# shield.net
KiCad netlist of a schematic drawn in EAGLE
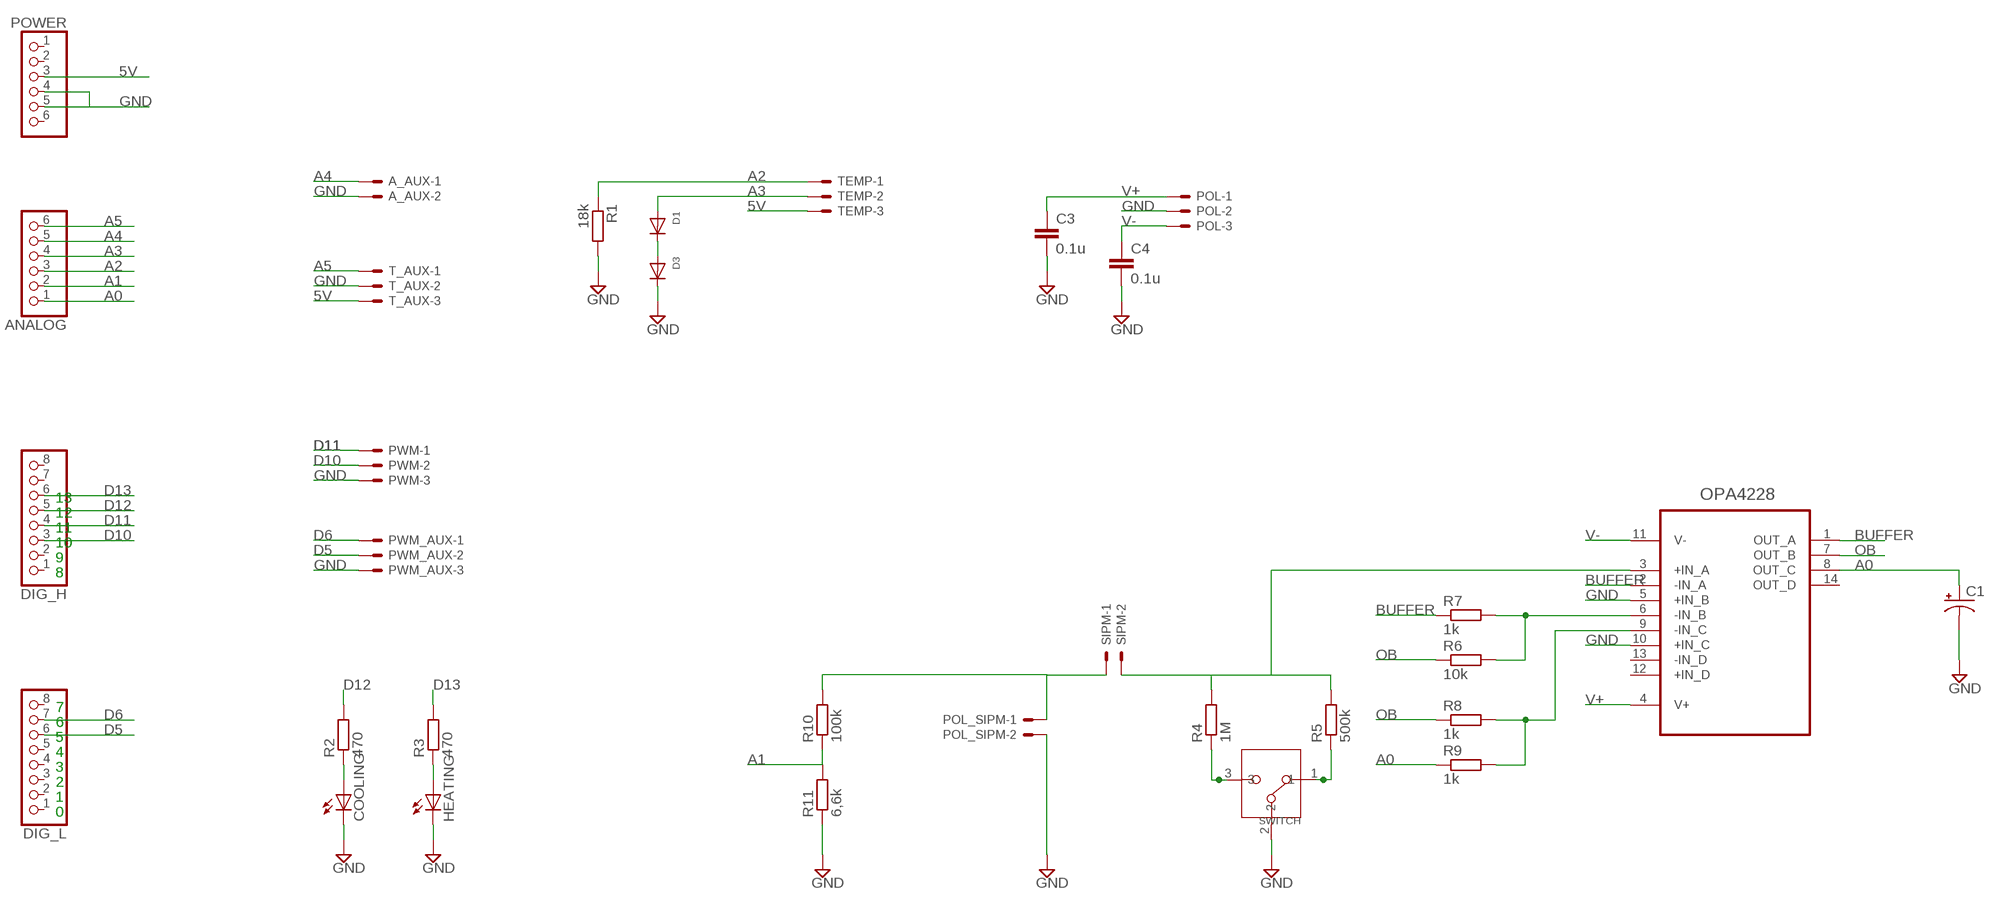
[diagram p0: schematic, sheet 1]

(export (version "E")
  (design (tool "Eeschema 10.0.6"))
  (components
    (comp (ref "ANALOG")
      (value "PINHD-1X6")
      (footprint "eagle-import:1X06")
      (libsource (lib "eagle-import") (part "PINHD-1X6"))
    )
    (comp (ref "A_AUX")
      (value "22-23-2021")
      (footprint "eagle-import:22-23-2021")
      (fields (field (name "MF") "MOLEX"))
      (libsource (lib "eagle-import") (part "22-23-2021"))
    )
    (comp (ref "C1")
      (value "CPOL-USSMCC")
      (footprint "eagle-import:SMC_C")
      (libsource (lib "eagle-import") (part "CPOL-USSMCC"))
    )
    (comp (ref "C3")
      (value "0.1u")
      (footprint "eagle-import:C0805K")
      (libsource (lib "eagle-import") (part "C-EUC0805K"))
    )
    (comp (ref "C4")
      (value "0.1u")
      (footprint "eagle-import:C0805K")
      (libsource (lib "eagle-import") (part "C-EUC0805K"))
    )
    (comp (ref "COOLING")
      (value "LEDSMT1206")
      (footprint "eagle-import:1206")
      (libsource (lib "eagle-import") (part "LEDSMT1206"))
    )
    (comp (ref "D1")
      (value "DIODEDO-1N4148")
      (footprint "eagle-import:DO-1N4148")
      (libsource (lib "eagle-import") (part "DIODEDO-1N4148"))
    )
    (comp (ref "D3")
      (value "DIODEDO-1N4148")
      (footprint "eagle-import:DO-1N4148")
      (libsource (lib "eagle-import") (part "DIODEDO-1N4148"))
    )
    (comp (ref "DIG_H")
      (value "PINHD-1X8")
      (footprint "eagle-import:1X08")
      (libsource (lib "eagle-import") (part "PINHD-1X8"))
    )
    (comp (ref "DIG_L")
      (value "PINHD-1X8")
      (footprint "eagle-import:1X08")
      (libsource (lib "eagle-import") (part "PINHD-1X8"))
    )
    (comp (ref "HEATING")
      (value "LEDSMT1206")
      (footprint "eagle-import:1206")
      (libsource (lib "eagle-import") (part "LEDSMT1206"))
    )
    (comp (ref "OPA4228")
      (value "OPA4228UA")
      (footprint "eagle-import:SOIC127P600X175-14N")
      (fields (field (name "DIGI-KEY_PART_NUMBER") "OPA4228UA-ND") (field (name "MF") "Texas Instruments"))
      (libsource (lib "eagle-import") (part "OPA4228UA"))
    )
    (comp (ref "POL")
      (value "22-23-2031")
      (footprint "eagle-import:22-23-2031")
      (fields (field (name "MF") "MOLEX"))
      (libsource (lib "eagle-import") (part "22-23-2031"))
    )
    (comp (ref "POL_SIPM")
      (value "22-23-2021")
      (footprint "eagle-import:22-23-2021")
      (fields (field (name "MF") "MOLEX"))
      (libsource (lib "eagle-import") (part "22-23-2021"))
    )
    (comp (ref "POWER")
      (value "PINHD-1X6")
      (footprint "eagle-import:1X06")
      (libsource (lib "eagle-import") (part "PINHD-1X6"))
    )
    (comp (ref "PWM")
      (value "22-23-2031")
      (footprint "eagle-import:22-23-2031")
      (fields (field (name "MF") "MOLEX"))
      (libsource (lib "eagle-import") (part "22-23-2031"))
    )
    (comp (ref "PWM_AUX")
      (value "22-23-2031")
      (footprint "eagle-import:22-23-2031")
      (fields (field (name "MF") "MOLEX"))
      (libsource (lib "eagle-import") (part "22-23-2031"))
    )
    (comp (ref "R1")
      (value "18k")
      (footprint "eagle-import:0309_12")
      (libsource (lib "eagle-import") (part "R-EU_0309/12"))
    )
    (comp (ref "R2")
      (value "470")
      (footprint "eagle-import:R0805W")
      (libsource (lib "eagle-import") (part "resistor_R-EU_R0805W"))
    )
    (comp (ref "R3")
      (value "470")
      (footprint "eagle-import:R0805W")
      (libsource (lib "eagle-import") (part "resistor_R-EU_R0805W"))
    )
    (comp (ref "R4")
      (value "1M")
      (footprint "eagle-import:R0805W")
      (libsource (lib "eagle-import") (part "resistor_R-EU_R0805W"))
    )
    (comp (ref "R5")
      (value "500k")
      (footprint "eagle-import:R0805W")
      (libsource (lib "eagle-import") (part "resistor_R-EU_R0805W"))
    )
    (comp (ref "R6")
      (value "10k")
      (footprint "eagle-import:R0805W")
      (libsource (lib "eagle-import") (part "resistor_R-EU_R0805W"))
    )
    (comp (ref "R7")
      (value "1k")
      (footprint "eagle-import:R0805W")
      (libsource (lib "eagle-import") (part "resistor_R-EU_R0805W"))
    )
    (comp (ref "R8")
      (value "1k")
      (footprint "eagle-import:R0805W")
      (libsource (lib "eagle-import") (part "resistor_R-EU_R0805W"))
    )
    (comp (ref "R9")
      (value "1k")
      (footprint "eagle-import:R0805W")
      (libsource (lib "eagle-import") (part "resistor_R-EU_R0805W"))
    )
    (comp (ref "R10")
      (value "100k")
      (footprint "eagle-import:R0805W")
      (libsource (lib "eagle-import") (part "resistor_R-EU_R0805W"))
    )
    (comp (ref "R11")
      (value "6,6k")
      (footprint "eagle-import:R0805W")
      (libsource (lib "eagle-import") (part "resistor_R-EU_R0805W"))
    )
    (comp (ref "SIPM")
      (value "22-23-2021")
      (footprint "eagle-import:22-23-2021")
      (fields (field (name "MF") "MOLEX"))
      (libsource (lib "eagle-import") (part "22-23-2021"))
    )
    (comp (ref "SWITCH")
      (value "DIP-SLIDE-SWITCH(3P-11.6X4.0X5.4+2.0MM)-EG1218")
      (footprint "eagle-import:SW3-2.5-11.6X4.0X5.4+2.0MM")
      (fields (field (name "MF") "E-Switch") (field (name "MP") "EG1218"))
      (libsource (lib "eagle-import") (part "DIP-SLIDE-SWITCH(3P-11.6X4.0X5.4+2.0MM)-EG1218"))
    )
    (comp (ref "TEMP")
      (value "22-23-2031")
      (footprint "eagle-import:22-23-2031")
      (fields (field (name "MF") "MOLEX"))
      (libsource (lib "eagle-import") (part "22-23-2031"))
    )
    (comp (ref "T_AUX")
      (value "22-23-2031")
      (footprint "eagle-import:22-23-2031")
      (fields (field (name "MF") "MOLEX"))
      (libsource (lib "eagle-import") (part "22-23-2031"))
    )
  )
  (nets
    (net (code "1") (name "/5V") (class "Default")
      (node (ref "POWER") (pin "3") (pinfunction "3_3") (pintype "passive"))
      (node (ref "TEMP") (pin "3") (pinfunction "S_3") (pintype "passive"))
      (node (ref "T_AUX") (pin "3") (pinfunction "S_3") (pintype "passive"))
    )
    (net (code "2") (name "/A0") (class "Default")
      (node (ref "ANALOG") (pin "1") (pinfunction "1_1") (pintype "passive"))
      (node (ref "C1") (pin "+") (pinfunction "+_+") (pintype "passive"))
      (node (ref "OPA4228") (pin "8") (pinfunction "OUT_C_8") (pintype "output"))
      (node (ref "R9") (pin "1") (pinfunction "1_1") (pintype "passive"))
    )
    (net (code "3") (name "/A1") (class "Default")
      (node (ref "ANALOG") (pin "2") (pinfunction "2_2") (pintype "passive"))
      (node (ref "R10") (pin "1") (pinfunction "1_1") (pintype "passive"))
      (node (ref "R11") (pin "2") (pinfunction "2_2") (pintype "passive"))
    )
    (net (code "4") (name "/A2") (class "Default")
      (node (ref "ANALOG") (pin "3") (pinfunction "3_3") (pintype "passive"))
      (node (ref "R1") (pin "1") (pinfunction "1_1") (pintype "passive"))
      (node (ref "TEMP") (pin "1") (pinfunction "S_1") (pintype "passive"))
    )
    (net (code "5") (name "/A3") (class "Default")
      (node (ref "ANALOG") (pin "4") (pinfunction "4_4") (pintype "passive"))
      (node (ref "D1") (pin "A") (pinfunction "A_A") (pintype "passive"))
      (node (ref "TEMP") (pin "2") (pinfunction "S_2") (pintype "passive"))
    )
    (net (code "6") (name "/A4") (class "Default")
      (node (ref "ANALOG") (pin "5") (pinfunction "5_5") (pintype "passive"))
      (node (ref "A_AUX") (pin "1") (pinfunction "S_1") (pintype "passive"))
    )
    (net (code "7") (name "/A5") (class "Default")
      (node (ref "ANALOG") (pin "6") (pinfunction "6_6") (pintype "passive"))
      (node (ref "T_AUX") (pin "1") (pinfunction "S_1") (pintype "passive"))
    )
    (net (code "8") (name "/BUFFER") (class "Default")
      (node (ref "OPA4228") (pin "1") (pinfunction "OUT_A_1") (pintype "output"))
      (node (ref "OPA4228") (pin "2") (pinfunction "-IN_A_2") (pintype "input"))
      (node (ref "R7") (pin "1") (pinfunction "1_1") (pintype "passive"))
    )
    (net (code "9") (name "/D5") (class "Default")
      (node (ref "DIG_L") (pin "6") (pinfunction "6_6") (pintype "passive"))
      (node (ref "PWM_AUX") (pin "2") (pinfunction "S_2") (pintype "passive"))
    )
    (net (code "10") (name "/D6") (class "Default")
      (node (ref "DIG_L") (pin "7") (pinfunction "7_7") (pintype "passive"))
      (node (ref "PWM_AUX") (pin "1") (pinfunction "S_1") (pintype "passive"))
    )
    (net (code "11") (name "/D10") (class "Default")
      (node (ref "DIG_H") (pin "3") (pinfunction "3_3") (pintype "passive"))
      (node (ref "PWM") (pin "2") (pinfunction "S_2") (pintype "passive"))
    )
    (net (code "12") (name "/D11") (class "Default")
      (node (ref "DIG_H") (pin "4") (pinfunction "4_4") (pintype "passive"))
      (node (ref "PWM") (pin "1") (pinfunction "S_1") (pintype "passive"))
    )
    (net (code "13") (name "/D12") (class "Default")
      (node (ref "DIG_H") (pin "5") (pinfunction "5_5") (pintype "passive"))
      (node (ref "R2") (pin "2") (pinfunction "2_2") (pintype "passive"))
    )
    (net (code "14") (name "/D13") (class "Default")
      (node (ref "DIG_H") (pin "6") (pinfunction "6_6") (pintype "passive"))
      (node (ref "R3") (pin "2") (pinfunction "2_2") (pintype "passive"))
    )
    (net (code "15") (name "/OB") (class "Default")
      (node (ref "OPA4228") (pin "7") (pinfunction "OUT_B_7") (pintype "output"))
      (node (ref "R6") (pin "1") (pinfunction "1_1") (pintype "passive"))
      (node (ref "R8") (pin "1") (pinfunction "1_1") (pintype "passive"))
    )
    (net (code "16") (name "/V+") (class "Default")
      (node (ref "C3") (pin "1") (pinfunction "1_1") (pintype "passive"))
      (node (ref "OPA4228") (pin "4") (pinfunction "V+_4") (pintype "power_in"))
      (node (ref "POL") (pin "1") (pinfunction "S_1") (pintype "passive"))
    )
    (net (code "17") (name "/V-") (class "Default")
      (node (ref "C4") (pin "1") (pinfunction "1_1") (pintype "passive"))
      (node (ref "OPA4228") (pin "11") (pinfunction "V-_11") (pintype "power_in"))
      (node (ref "POL") (pin "3") (pinfunction "S_3") (pintype "passive"))
    )
    (net (code "18") (name "GND") (class "Default")
      (node (ref "A_AUX") (pin "2") (pinfunction "S_2") (pintype "passive"))
      (node (ref "C1") (pin "-") (pinfunction "-_-") (pintype "passive"))
      (node (ref "C3") (pin "2") (pinfunction "2_2") (pintype "passive"))
      (node (ref "C4") (pin "2") (pinfunction "2_2") (pintype "passive"))
      (node (ref "COOLING") (pin "C") (pinfunction "C_C") (pintype "passive"))
      (node (ref "D3") (pin "C") (pinfunction "C_C") (pintype "passive"))
      (node (ref "HEATING") (pin "C") (pinfunction "C_C") (pintype "passive"))
      (node (ref "OPA4228") (pin "10") (pinfunction "+IN_C_10") (pintype "input"))
      (node (ref "OPA4228") (pin "5") (pinfunction "+IN_B_5") (pintype "input"))
      (node (ref "POL") (pin "2") (pinfunction "S_2") (pintype "passive"))
      (node (ref "POL_SIPM") (pin "2") (pinfunction "S_2") (pintype "passive"))
      (node (ref "POWER") (pin "4") (pinfunction "4_4") (pintype "passive"))
      (node (ref "POWER") (pin "5") (pinfunction "5_5") (pintype "passive"))
      (node (ref "PWM") (pin "3") (pinfunction "S_3") (pintype "passive"))
      (node (ref "PWM_AUX") (pin "3") (pinfunction "S_3") (pintype "passive"))
      (node (ref "R1") (pin "2") (pinfunction "2_2") (pintype "passive"))
      (node (ref "R11") (pin "1") (pinfunction "1_1") (pintype "passive"))
      (node (ref "SWITCH") (pin "2") (pinfunction "2_2") (pintype "bidirectional"))
      (node (ref "T_AUX") (pin "2") (pinfunction "S_2") (pintype "passive"))
    )
    (net (code "19") (name "Net-(COOLING-PadA)") (class "Default")
      (node (ref "COOLING") (pin "A") (pinfunction "A_A") (pintype "passive"))
      (node (ref "R2") (pin "1") (pinfunction "1_1") (pintype "passive"))
    )
    (net (code "20") (name "Net-(D1-PadC)") (class "Default")
      (node (ref "D1") (pin "C") (pinfunction "C_C") (pintype "passive"))
      (node (ref "D3") (pin "A") (pinfunction "A_A") (pintype "passive"))
    )
    (net (code "21") (name "Net-(HEATING-PadA)") (class "Default")
      (node (ref "HEATING") (pin "A") (pinfunction "A_A") (pintype "passive"))
      (node (ref "R3") (pin "1") (pinfunction "1_1") (pintype "passive"))
    )
    (net (code "22") (name "Net-(OPA4228-+IN_A)") (class "Default")
      (node (ref "OPA4228") (pin "3") (pinfunction "+IN_A_3") (pintype "input"))
      (node (ref "R4") (pin "2") (pinfunction "2_2") (pintype "passive"))
      (node (ref "R5") (pin "2") (pinfunction "2_2") (pintype "passive"))
      (node (ref "SIPM") (pin "2") (pinfunction "S_2") (pintype "passive"))
    )
    (net (code "23") (name "Net-(OPA4228--IN_B)") (class "Default")
      (node (ref "OPA4228") (pin "6") (pinfunction "-IN_B_6") (pintype "input"))
      (node (ref "R6") (pin "2") (pinfunction "2_2") (pintype "passive"))
      (node (ref "R7") (pin "2") (pinfunction "2_2") (pintype "passive"))
    )
    (net (code "24") (name "Net-(OPA4228--IN_C)") (class "Default")
      (node (ref "OPA4228") (pin "9") (pinfunction "-IN_C_9") (pintype "input"))
      (node (ref "R8") (pin "2") (pinfunction "2_2") (pintype "passive"))
      (node (ref "R9") (pin "2") (pinfunction "2_2") (pintype "passive"))
    )
    (net (code "25") (name "Net-(POL_SIPMA-S)") (class "Default")
      (node (ref "POL_SIPM") (pin "1") (pinfunction "S_1") (pintype "passive"))
      (node (ref "R10") (pin "2") (pinfunction "2_2") (pintype "passive"))
      (node (ref "SIPM") (pin "1") (pinfunction "S_1") (pintype "passive"))
    )
    (net (code "26") (name "Net-(R4-Pad1)") (class "Default")
      (node (ref "R4") (pin "1") (pinfunction "1_1") (pintype "passive"))
      (node (ref "SWITCH") (pin "3") (pinfunction "3_3") (pintype "bidirectional"))
    )
    (net (code "27") (name "Net-(R5-Pad1)") (class "Default")
      (node (ref "R5") (pin "1") (pinfunction "1_1") (pintype "passive"))
      (node (ref "SWITCH") (pin "1") (pinfunction "1_1") (pintype "bidirectional"))
    )
    (net (code "28") (name "unconnected-(DIG_H-Pad1)") (class "Default")
      (node (ref "DIG_H") (pin "1") (pinfunction "1_1") (pintype "passive"))
    )
    (net (code "29") (name "unconnected-(DIG_H-Pad2)") (class "Default")
      (node (ref "DIG_H") (pin "2") (pinfunction "2_2") (pintype "passive"))
    )
    (net (code "30") (name "unconnected-(DIG_H-Pad7)") (class "Default")
      (node (ref "DIG_H") (pin "7") (pinfunction "7_7") (pintype "passive"))
    )
    (net (code "31") (name "unconnected-(DIG_H-Pad8)") (class "Default")
      (node (ref "DIG_H") (pin "8") (pinfunction "8_8") (pintype "passive"))
    )
    (net (code "32") (name "unconnected-(DIG_L-Pad1)") (class "Default")
      (node (ref "DIG_L") (pin "1") (pinfunction "1_1") (pintype "passive"))
    )
    (net (code "33") (name "unconnected-(DIG_L-Pad2)") (class "Default")
      (node (ref "DIG_L") (pin "2") (pinfunction "2_2") (pintype "passive"))
    )
    (net (code "34") (name "unconnected-(DIG_L-Pad3)") (class "Default")
      (node (ref "DIG_L") (pin "3") (pinfunction "3_3") (pintype "passive"))
    )
    (net (code "35") (name "unconnected-(DIG_L-Pad4)") (class "Default")
      (node (ref "DIG_L") (pin "4") (pinfunction "4_4") (pintype "passive"))
    )
    (net (code "36") (name "unconnected-(DIG_L-Pad5)") (class "Default")
      (node (ref "DIG_L") (pin "5") (pinfunction "5_5") (pintype "passive"))
    )
    (net (code "37") (name "unconnected-(DIG_L-Pad8)") (class "Default")
      (node (ref "DIG_L") (pin "8") (pinfunction "8_8") (pintype "passive"))
    )
    (net (code "38") (name "unconnected-(OPA4228-+IN_D-Pad12)") (class "Default")
      (node (ref "OPA4228") (pin "12") (pinfunction "+IN_D_12") (pintype "input"))
    )
    (net (code "39") (name "unconnected-(OPA4228--IN_D-Pad13)") (class "Default")
      (node (ref "OPA4228") (pin "13") (pinfunction "-IN_D_13") (pintype "input"))
    )
    (net (code "40") (name "unconnected-(OPA4228-OUT_D-Pad14)") (class "Default")
      (node (ref "OPA4228") (pin "14") (pinfunction "OUT_D_14") (pintype "output"))
    )
    (net (code "41") (name "unconnected-(POWER-Pad1)") (class "Default")
      (node (ref "POWER") (pin "1") (pinfunction "1_1") (pintype "passive"))
    )
    (net (code "42") (name "unconnected-(POWER-Pad2)") (class "Default")
      (node (ref "POWER") (pin "2") (pinfunction "2_2") (pintype "passive"))
    )
    (net (code "43") (name "unconnected-(POWER-Pad6)") (class "Default")
      (node (ref "POWER") (pin "6") (pinfunction "6_6") (pintype "passive"))
    )
  )
)
